# protel_wireless_receiver.net
KiCad netlist of a schematic drawn in Altium Designer
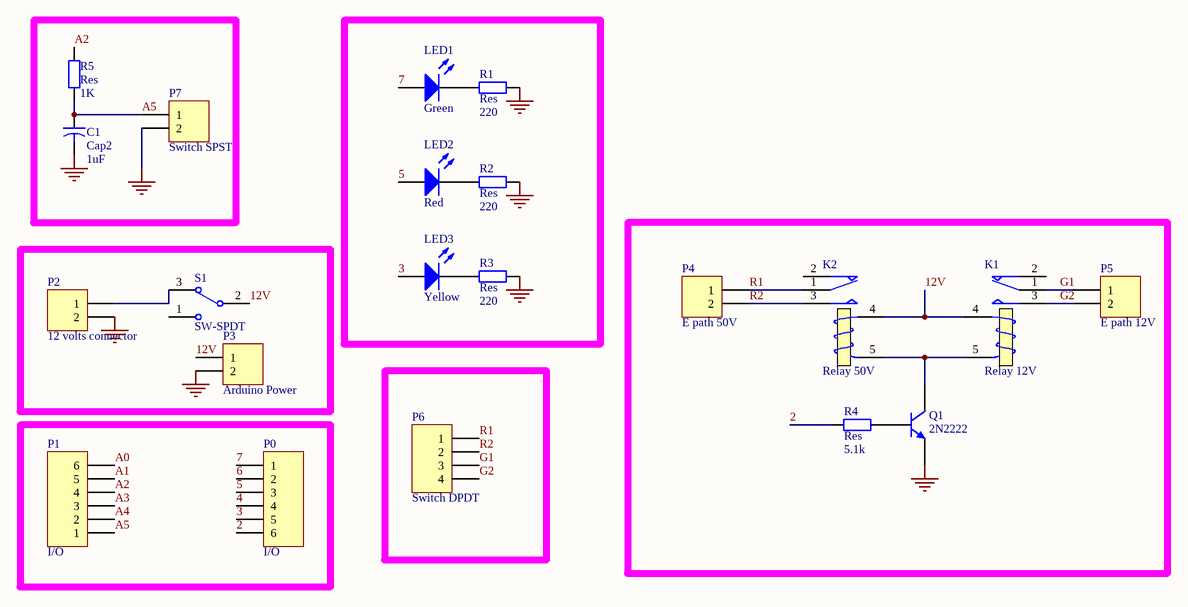
[diagram p0: protel_wireless_receiver.SchDoc]

(export (version "E")
  (design (tool "Eeschema 10.0.6"))
  (components
    (comp (ref "C1")
      (value "Cap2")
      (footprint "CAPR5-4X5")
      (description "Capacitor")
      (fields (field (name "ALTIUM_VALUE") "1uF") (field (name "PUBLISHER") "Altium Limited"))
      (libsource (lib "Miscellaneous Devices") (part "Cap2"))
    )
    (comp (ref "K1")
      (value "Relay 12V")
      (footprint "relay 6pin")
      (description "SPDT Relay")
      (fields (field (name "PUBLISHER") "Altium Limited"))
      (libsource (lib "Miscellaneous Devices") (part "Relay"))
    )
    (comp (ref "K2")
      (value "Relay 50V")
      (footprint "JS relay")
      (description "SPDT Relay")
      (fields (field (name "PUBLISHER") "Altium Limited"))
      (libsource (lib "") (part "Relay_1"))
    )
    (comp (ref "LED1")
      (value "Green")
      (footprint "LED-1")
      (description "Typical RED GaAs LED")
      (fields (field (name "PUBLISHER") "Altium Limited"))
      (libsource (lib "Miscellaneous Devices") (part "LED1"))
    )
    (comp (ref "LED2")
      (value "Red")
      (footprint "LED-1")
      (description "Typical RED GaAs LED")
      (fields (field (name "PUBLISHER") "Altium Limited"))
      (libsource (lib "Miscellaneous Devices") (part "LED1"))
    )
    (comp (ref "LED3")
      (value "Yellow")
      (footprint "LED-1")
      (description "Typical RED GaAs LED")
      (fields (field (name "PUBLISHER") "Altium Limited"))
      (libsource (lib "Miscellaneous Devices") (part "LED1"))
    )
    (comp (ref "P0")
      (value "I/O")
      (footprint "HDR1X6")
      (description "Header, 6-Pin")
      (fields (field (name "PUBLISHER") "Altium Limited"))
      (libsource (lib "Miscellaneous Connectors") (part "Header 6"))
    )
    (comp (ref "P1")
      (value "I/O")
      (footprint "HDR1X6")
      (description "Header, 6-Pin")
      (fields (field (name "PUBLISHER") "Altium Limited"))
      (libsource (lib "") (part "Header 6_1"))
    )
    (comp (ref "P2")
      (value "12 volts connector")
      (footprint "HDR1X2")
      (description "Header, 2-Pin")
      (fields (field (name "PUBLISHER") "Altium Limited"))
      (libsource (lib "") (part "Header 2_1"))
    )
    (comp (ref "P3")
      (value "Arduino Power")
      (footprint "HDR1X2")
      (description "Header, 2-Pin")
      (fields (field (name "PUBLISHER") "Altium Limited"))
      (libsource (lib "Miscellaneous Connectors") (part "Header 2"))
    )
    (comp (ref "P4")
      (value "E path 50V")
      (footprint "HDR1X2")
      (description "Header, 2-Pin")
      (fields (field (name "PUBLISHER") "Altium Limited"))
      (libsource (lib "") (part "Header 2_1"))
    )
    (comp (ref "P5")
      (value "E path 12V")
      (footprint "HDR1X2")
      (description "Header, 2-Pin")
      (fields (field (name "PUBLISHER") "Altium Limited"))
      (libsource (lib "Miscellaneous Connectors") (part "Header 2"))
    )
    (comp (ref "P6")
      (value "Switch DPDT")
      (footprint "HDR1X4")
      (description "Header, 4-Pin")
      (fields (field (name "PUBLISHER") "Altium Limited"))
      (libsource (lib "Miscellaneous Connectors") (part "Header 4"))
    )
    (comp (ref "P7")
      (value "Switch SPST")
      (footprint "HDR1X2")
      (description "Header, 2-Pin")
      (fields (field (name "PUBLISHER") "Altium Limited"))
      (libsource (lib "Miscellaneous Connectors") (part "Header 2"))
    )
    (comp (ref "Q1")
      (value "2N2222")
      (footprint "CAN-3/D5.9")
      (description "General Purpose Transistor NPN Silicon")
      (fields (field (name "PUBLISHER") "Altium Limited"))
      (libsource (lib "Motorola Discrete BJT") (part "2N2222"))
    )
    (comp (ref "R1")
      (value "Res")
      (footprint "AXIAL-0.4")
      (description "Resistor")
      (fields (field (name "ALTIUM_VALUE") "220") (field (name "PUBLISHER") "Altium Limited"))
      (libsource (lib "Miscellaneous Devices") (part "Res2"))
    )
    (comp (ref "R2")
      (value "Res")
      (footprint "AXIAL-0.4")
      (description "Resistor")
      (fields (field (name "ALTIUM_VALUE") "220") (field (name "PUBLISHER") "Altium Limited"))
      (libsource (lib "Miscellaneous Devices") (part "Res2"))
    )
    (comp (ref "R3")
      (value "Res")
      (footprint "AXIAL-0.4")
      (description "Resistor")
      (fields (field (name "ALTIUM_VALUE") "220") (field (name "PUBLISHER") "Altium Limited"))
      (libsource (lib "Miscellaneous Devices") (part "Res2"))
    )
    (comp (ref "R4")
      (value "Res")
      (footprint "AXIAL-0.4")
      (description "Resistor")
      (fields (field (name "ALTIUM_VALUE") "5.1k") (field (name "PUBLISHER") "Altium Limited"))
      (libsource (lib "Miscellaneous Devices") (part "Res2"))
    )
    (comp (ref "R5")
      (value "Res")
      (footprint "AXIAL-0.4")
      (description "Resistor")
      (fields (field (name "ALTIUM_VALUE") "1K") (field (name "PUBLISHER") "Altium Limited"))
      (libsource (lib "") (part "Res2_1"))
    )
    (comp (ref "S1")
      (value "SW-SPDT")
      (footprint "SPDT")
      (description "SPDT Subminiature Toggle Switch, Right Angle Mounting, Vertical Actuation")
      (fields (field (name "PUBLISHER") "Altium Limited"))
      (libsource (lib "Miscellaneous Devices") (part "SW-SPDT"))
    )
  )
  (nets
    (net (code "1") (name "/2") (class "Default")
      (node (ref "P0") (pin "6") (pinfunction "6_6") (pintype "passive"))
      (node (ref "R4") (pin "1") (pinfunction "1_1") (pintype "passive"))
    )
    (net (code "2") (name "/3") (class "Default")
      (node (ref "LED3") (pin "1") (pinfunction "A_1") (pintype "passive"))
      (node (ref "P0") (pin "5") (pinfunction "5_5") (pintype "passive"))
    )
    (net (code "3") (name "/4") (class "Default")
      (node (ref "P0") (pin "4") (pinfunction "4_4") (pintype "passive"))
    )
    (net (code "4") (name "/5") (class "Default")
      (node (ref "LED2") (pin "1") (pinfunction "A_1") (pintype "passive"))
      (node (ref "P0") (pin "3") (pinfunction "3_3") (pintype "passive"))
    )
    (net (code "5") (name "/6") (class "Default")
      (node (ref "P0") (pin "2") (pinfunction "2_2") (pintype "passive"))
    )
    (net (code "6") (name "/7") (class "Default")
      (node (ref "LED1") (pin "1") (pinfunction "A_1") (pintype "passive"))
      (node (ref "P0") (pin "1") (pinfunction "1_1") (pintype "passive"))
    )
    (net (code "7") (name "/12V") (class "Default")
      (node (ref "K1") (pin "4") (pinfunction "T1_4") (pintype "passive"))
      (node (ref "K2") (pin "4") (pinfunction "T1_4") (pintype "passive"))
      (node (ref "P3") (pin "1") (pinfunction "1_1") (pintype "passive"))
      (node (ref "S1") (pin "2") (pinfunction "2_2") (pintype "passive"))
    )
    (net (code "8") (name "/A0") (class "Default")
      (node (ref "P1") (pin "6") (pinfunction "6_6") (pintype "passive"))
    )
    (net (code "9") (name "/A1") (class "Default")
      (node (ref "P1") (pin "5") (pinfunction "5_5") (pintype "passive"))
    )
    (net (code "10") (name "/A2") (class "Default")
      (node (ref "P1") (pin "4") (pinfunction "4_4") (pintype "passive"))
      (node (ref "R5") (pin "2") (pinfunction "2_2") (pintype "passive"))
    )
    (net (code "11") (name "/A3") (class "Default")
      (node (ref "P1") (pin "3") (pinfunction "3_3") (pintype "passive"))
    )
    (net (code "12") (name "/A4") (class "Default")
      (node (ref "P1") (pin "2") (pinfunction "2_2") (pintype "passive"))
    )
    (net (code "13") (name "/A5") (class "Default")
      (node (ref "C1") (pin "1") (pinfunction "1_1") (pintype "passive"))
      (node (ref "P1") (pin "1") (pinfunction "1_1") (pintype "passive"))
      (node (ref "P7") (pin "1") (pinfunction "1_1") (pintype "passive"))
      (node (ref "R5") (pin "1") (pinfunction "1_1") (pintype "passive"))
    )
    (net (code "14") (name "/G1") (class "Default")
      (node (ref "K1") (pin "1") (pinfunction "COM_1") (pintype "passive"))
      (node (ref "P5") (pin "1") (pinfunction "1_1") (pintype "passive"))
      (node (ref "P6") (pin "3") (pinfunction "3_3") (pintype "passive"))
    )
    (net (code "15") (name "/G2") (class "Default")
      (node (ref "K1") (pin "3") (pinfunction "NO_3") (pintype "passive"))
      (node (ref "P5") (pin "2") (pinfunction "2_2") (pintype "passive"))
      (node (ref "P6") (pin "4") (pinfunction "4_4") (pintype "passive"))
    )
    (net (code "16") (name "/R1") (class "Default")
      (node (ref "K2") (pin "1") (pinfunction "COM_1") (pintype "passive"))
      (node (ref "P4") (pin "1") (pinfunction "1_1") (pintype "passive"))
      (node (ref "P6") (pin "1") (pinfunction "1_1") (pintype "passive"))
    )
    (net (code "17") (name "/R2") (class "Default")
      (node (ref "K2") (pin "3") (pinfunction "NO_3") (pintype "passive"))
      (node (ref "P4") (pin "2") (pinfunction "2_2") (pintype "passive"))
      (node (ref "P6") (pin "2") (pinfunction "2_2") (pintype "passive"))
    )
    (net (code "18") (name "GND") (class "Default")
      (node (ref "C1") (pin "2") (pinfunction "2_2") (pintype "passive"))
      (node (ref "P2") (pin "2") (pinfunction "2_2") (pintype "passive"))
      (node (ref "P3") (pin "2") (pinfunction "2_2") (pintype "passive"))
      (node (ref "P7") (pin "2") (pinfunction "2_2") (pintype "passive"))
      (node (ref "Q1") (pin "1") (pinfunction "E_1") (pintype "passive"))
      (node (ref "R1") (pin "2") (pinfunction "2_2") (pintype "passive"))
      (node (ref "R2") (pin "2") (pinfunction "2_2") (pintype "passive"))
      (node (ref "R3") (pin "2") (pinfunction "2_2") (pintype "passive"))
    )
    (net (code "19") (name "Net-(K1-T2)") (class "Default")
      (node (ref "K1") (pin "5") (pinfunction "T2_5") (pintype "passive"))
      (node (ref "K2") (pin "5") (pinfunction "T2_5") (pintype "passive"))
      (node (ref "Q1") (pin "3") (pinfunction "C_3") (pintype "passive"))
    )
    (net (code "20") (name "Net-(LED1-K)") (class "Default")
      (node (ref "LED1") (pin "2") (pinfunction "K_2") (pintype "passive"))
      (node (ref "R1") (pin "1") (pinfunction "1_1") (pintype "passive"))
    )
    (net (code "21") (name "Net-(LED2-K)") (class "Default")
      (node (ref "LED2") (pin "2") (pinfunction "K_2") (pintype "passive"))
      (node (ref "R2") (pin "1") (pinfunction "1_1") (pintype "passive"))
    )
    (net (code "22") (name "Net-(LED3-K)") (class "Default")
      (node (ref "LED3") (pin "2") (pinfunction "K_2") (pintype "passive"))
      (node (ref "R3") (pin "1") (pinfunction "1_1") (pintype "passive"))
    )
    (net (code "23") (name "Net-(P2-Pad1)") (class "Default")
      (node (ref "P2") (pin "1") (pinfunction "1_1") (pintype "passive"))
      (node (ref "S1") (pin "3") (pinfunction "3_3") (pintype "passive"))
    )
    (net (code "24") (name "Net-(Q1-B)") (class "Default")
      (node (ref "Q1") (pin "2") (pinfunction "B_2") (pintype "passive"))
      (node (ref "R4") (pin "2") (pinfunction "2_2") (pintype "passive"))
    )
    (net (code "25") (name "unconnected-(K1-NC-Pad2)") (class "Default")
      (node (ref "K1") (pin "2") (pinfunction "NC_2") (pintype "passive"))
    )
    (net (code "26") (name "unconnected-(K2-NC-Pad2)") (class "Default")
      (node (ref "K2") (pin "2") (pinfunction "NC_2") (pintype "passive"))
    )
    (net (code "27") (name "unconnected-(S1-Pad1)") (class "Default")
      (node (ref "S1") (pin "1") (pinfunction "1_1") (pintype "passive"))
    )
  )
)
